# FPGA_Socket.net
KiCad netlist of a schematic drawn in Altium Designer
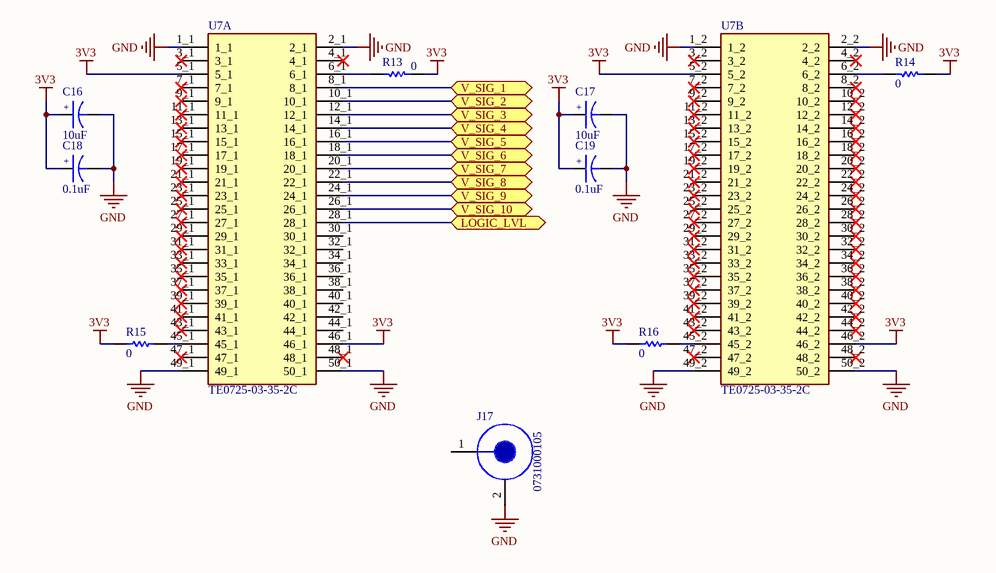
[diagram p0: FPGA_Socket.SchDoc]

(export (version "E")
  (design (tool "Eeschema 10.0.6"))
  (components
    (comp (ref "C16")
      (value "10uF")
      (footprint "0603C")
      (description "Cap Poly")
      (libsource (lib "GENERIC_LIB") (part "CPoly"))
    )
    (comp (ref "C17")
      (value "10uF")
      (footprint "0603C")
      (description "Cap Poly")
      (libsource (lib "GENERIC_LIB") (part "CPoly"))
    )
    (comp (ref "C18")
      (value "0.1uF")
      (footprint "0603C")
      (description "Cap Poly")
      (libsource (lib "GENERIC_LIB") (part "CPoly"))
    )
    (comp (ref "C19")
      (value "0.1uF")
      (footprint "0603C")
      (description "Cap Poly")
      (libsource (lib "GENERIC_LIB") (part "CPoly"))
    )
    (comp (ref "J17")
      (value "0731000105")
      (footprint "0731000105")
      (description "BNC Connector Jack, Female Socket 50Ohm Through Hole, Right Angle Solder")
      (libsource (lib "CON_LIB") (part "0731000105"))
    )
    (comp (ref "R13")
      (value "0")
      (footprint "0603C")
      (description "Resistor")
      (fields (field (name "TOLERANCE") "5%"))
      (libsource (lib "GENERIC_LIB") (part "R"))
    )
    (comp (ref "R14")
      (value "0")
      (footprint "0603C")
      (description "Resistor")
      (fields (field (name "TOLERANCE") "5%"))
      (libsource (lib "GENERIC_LIB") (part "R"))
    )
    (comp (ref "R15")
      (value "0")
      (footprint "0603C")
      (description "Resistor")
      (fields (field (name "TOLERANCE") "5%"))
      (libsource (lib "GENERIC_LIB") (part "R"))
    )
    (comp (ref "R16")
      (value "0")
      (footprint "0603C")
      (description "Resistor")
      (fields (field (name "TOLERANCE") "5%"))
      (libsource (lib "GENERIC_LIB") (part "R"))
    )
    (comp (ref "U7")
      (value "TE0725-03-35-2C")
      (footprint "MODULE_TE0725-03-35-2C")
      (description "TE0725 Embedded Module Artix-7 A35T 100MHz 32MB")
      (fields (field (name "MF") "Trenz Electronic GmbH"))
      (libsource (lib "IC_LOGIC_LIB") (part "TE0725-03-35-2C"))
    )
  )
  (nets
    (net (code "1") (name "/LOGIC_LVL") (class "Default")
      (node (ref "U7") (pin "28_1") (pinfunction "28_1_28_1") (pintype "passive"))
    )
    (net (code "2") (name "/V_SIG_1") (class "Default")
      (node (ref "U7") (pin "8_1") (pinfunction "8_1_8_1") (pintype "passive"))
    )
    (net (code "3") (name "/V_SIG_2") (class "Default")
      (node (ref "U7") (pin "10_1") (pinfunction "10_1_10_1") (pintype "passive"))
    )
    (net (code "4") (name "/V_SIG_3") (class "Default")
      (node (ref "U7") (pin "12_1") (pinfunction "12_1_12_1") (pintype "passive"))
    )
    (net (code "5") (name "/V_SIG_4") (class "Default")
      (node (ref "U7") (pin "14_1") (pinfunction "14_1_14_1") (pintype "passive"))
    )
    (net (code "6") (name "/V_SIG_5") (class "Default")
      (node (ref "U7") (pin "16_1") (pinfunction "16_1_16_1") (pintype "passive"))
    )
    (net (code "7") (name "/V_SIG_6") (class "Default")
      (node (ref "U7") (pin "18_1") (pinfunction "18_1_18_1") (pintype "passive"))
    )
    (net (code "8") (name "/V_SIG_7") (class "Default")
      (node (ref "U7") (pin "20_1") (pinfunction "20_1_20_1") (pintype "passive"))
    )
    (net (code "9") (name "/V_SIG_8") (class "Default")
      (node (ref "U7") (pin "22_1") (pinfunction "22_1_22_1") (pintype "passive"))
    )
    (net (code "10") (name "/V_SIG_9") (class "Default")
      (node (ref "U7") (pin "24_1") (pinfunction "24_1_24_1") (pintype "passive"))
    )
    (net (code "11") (name "/V_SIG_10") (class "Default")
      (node (ref "U7") (pin "26_1") (pinfunction "26_1_26_1") (pintype "passive"))
    )
    (net (code "12") (name "3V3") (class "Default")
      (node (ref "C16") (pin "1") (pinfunction "1_1") (pintype "passive"))
      (node (ref "C17") (pin "1") (pinfunction "1_1") (pintype "passive"))
      (node (ref "C18") (pin "1") (pinfunction "1_1") (pintype "passive"))
      (node (ref "C19") (pin "1") (pinfunction "1_1") (pintype "passive"))
      (node (ref "R13") (pin "1") (pinfunction "1_1") (pintype "passive"))
      (node (ref "R14") (pin "1") (pinfunction "1_1") (pintype "passive"))
      (node (ref "R15") (pin "1") (pinfunction "1_1") (pintype "passive"))
      (node (ref "R16") (pin "1") (pinfunction "1_1") (pintype "passive"))
      (node (ref "U7") (pin "46_1") (pinfunction "46_1_46_1") (pintype "passive"))
      (node (ref "U7") (pin "46_2") (pinfunction "46_2_46_2") (pintype "passive"))
      (node (ref "U7") (pin "5_1") (pinfunction "5_1_5_1") (pintype "passive"))
      (node (ref "U7") (pin "5_2") (pinfunction "5_2_5_2") (pintype "passive"))
    )
    (net (code "13") (name "GND") (class "Default")
      (node (ref "C16") (pin "2") (pinfunction "2_2") (pintype "passive"))
      (node (ref "C17") (pin "2") (pinfunction "2_2") (pintype "passive"))
      (node (ref "C18") (pin "2") (pinfunction "2_2") (pintype "passive"))
      (node (ref "C19") (pin "2") (pinfunction "2_2") (pintype "passive"))
      (node (ref "J17") (pin "2") (pinfunction "2_2") (pintype "passive"))
      (node (ref "U7") (pin "1_1") (pinfunction "1_1_1_1") (pintype "passive"))
      (node (ref "U7") (pin "1_2") (pinfunction "1_2_1_2") (pintype "passive"))
      (node (ref "U7") (pin "2_1") (pinfunction "2_1_2_1") (pintype "passive"))
      (node (ref "U7") (pin "2_2") (pinfunction "2_2_2_2") (pintype "passive"))
      (node (ref "U7") (pin "49_1") (pinfunction "49_1_49_1") (pintype "passive"))
      (node (ref "U7") (pin "49_2") (pinfunction "49_2_49_2") (pintype "passive"))
      (node (ref "U7") (pin "50_1") (pinfunction "50_1_50_1") (pintype "passive"))
      (node (ref "U7") (pin "50_2") (pinfunction "50_2_50_2") (pintype "passive"))
    )
    (net (code "14") (name "Net-(R13-Pad2)") (class "Default")
      (node (ref "R13") (pin "2") (pinfunction "2_2") (pintype "passive"))
      (node (ref "U7") (pin "6_1") (pinfunction "6_1_6_1") (pintype "passive"))
    )
    (net (code "15") (name "Net-(R14-Pad2)") (class "Default")
      (node (ref "R14") (pin "2") (pinfunction "2_2") (pintype "passive"))
      (node (ref "U7") (pin "6_2") (pinfunction "6_2_6_2") (pintype "passive"))
    )
    (net (code "16") (name "Net-(R15-Pad2)") (class "Default")
      (node (ref "R15") (pin "2") (pinfunction "2_2") (pintype "passive"))
      (node (ref "U7") (pin "45_1") (pinfunction "45_1_45_1") (pintype "passive"))
    )
    (net (code "17") (name "Net-(R16-Pad2)") (class "Default")
      (node (ref "R16") (pin "2") (pinfunction "2_2") (pintype "passive"))
      (node (ref "U7") (pin "45_2") (pinfunction "45_2_45_2") (pintype "passive"))
    )
    (net (code "18") (name "unconnected-(J17-Pad1)") (class "Default")
      (node (ref "J17") (pin "1") (pinfunction "1_1") (pintype "passive"))
    )
    (net (code "19") (name "unconnected-(U7-Pad3_1)") (class "Default")
      (node (ref "U7") (pin "3_1") (pinfunction "3_1_3_1") (pintype "passive+no_connect"))
    )
    (net (code "20") (name "unconnected-(U7-Pad3_2)") (class "Default")
      (node (ref "U7") (pin "3_2") (pinfunction "3_2_3_2") (pintype "passive+no_connect"))
    )
    (net (code "21") (name "unconnected-(U7-Pad4_1)") (class "Default")
      (node (ref "U7") (pin "4_1") (pinfunction "4_1_4_1") (pintype "passive+no_connect"))
    )
    (net (code "22") (name "unconnected-(U7-Pad4_2)") (class "Default")
      (node (ref "U7") (pin "4_2") (pinfunction "4_2_4_2") (pintype "passive+no_connect"))
    )
    (net (code "23") (name "unconnected-(U7-Pad7_1)") (class "Default")
      (node (ref "U7") (pin "7_1") (pinfunction "7_1_7_1") (pintype "passive+no_connect"))
    )
    (net (code "24") (name "unconnected-(U7-Pad7_2)") (class "Default")
      (node (ref "U7") (pin "7_2") (pinfunction "7_2_7_2") (pintype "passive+no_connect"))
    )
    (net (code "25") (name "unconnected-(U7-Pad8_2)") (class "Default")
      (node (ref "U7") (pin "8_2") (pinfunction "8_2_8_2") (pintype "passive+no_connect"))
    )
    (net (code "26") (name "unconnected-(U7-Pad9_1)") (class "Default")
      (node (ref "U7") (pin "9_1") (pinfunction "9_1_9_1") (pintype "passive+no_connect"))
    )
    (net (code "27") (name "unconnected-(U7-Pad9_2)") (class "Default")
      (node (ref "U7") (pin "9_2") (pinfunction "9_2_9_2") (pintype "passive+no_connect"))
    )
    (net (code "28") (name "unconnected-(U7-Pad10_2)") (class "Default")
      (node (ref "U7") (pin "10_2") (pinfunction "10_2_10_2") (pintype "passive+no_connect"))
    )
    (net (code "29") (name "unconnected-(U7-Pad11_1)") (class "Default")
      (node (ref "U7") (pin "11_1") (pinfunction "11_1_11_1") (pintype "passive+no_connect"))
    )
    (net (code "30") (name "unconnected-(U7-Pad11_2)") (class "Default")
      (node (ref "U7") (pin "11_2") (pinfunction "11_2_11_2") (pintype "passive+no_connect"))
    )
    (net (code "31") (name "unconnected-(U7-Pad12_2)") (class "Default")
      (node (ref "U7") (pin "12_2") (pinfunction "12_2_12_2") (pintype "passive+no_connect"))
    )
    (net (code "32") (name "unconnected-(U7-Pad13_1)") (class "Default")
      (node (ref "U7") (pin "13_1") (pinfunction "13_1_13_1") (pintype "passive+no_connect"))
    )
    (net (code "33") (name "unconnected-(U7-Pad13_2)") (class "Default")
      (node (ref "U7") (pin "13_2") (pinfunction "13_2_13_2") (pintype "passive+no_connect"))
    )
    (net (code "34") (name "unconnected-(U7-Pad14_2)") (class "Default")
      (node (ref "U7") (pin "14_2") (pinfunction "14_2_14_2") (pintype "passive+no_connect"))
    )
    (net (code "35") (name "unconnected-(U7-Pad15_1)") (class "Default")
      (node (ref "U7") (pin "15_1") (pinfunction "15_1_15_1") (pintype "passive+no_connect"))
    )
    (net (code "36") (name "unconnected-(U7-Pad15_2)") (class "Default")
      (node (ref "U7") (pin "15_2") (pinfunction "15_2_15_2") (pintype "passive+no_connect"))
    )
    (net (code "37") (name "unconnected-(U7-Pad16_2)") (class "Default")
      (node (ref "U7") (pin "16_2") (pinfunction "16_2_16_2") (pintype "passive+no_connect"))
    )
    (net (code "38") (name "unconnected-(U7-Pad17_1)") (class "Default")
      (node (ref "U7") (pin "17_1") (pinfunction "17_1_17_1") (pintype "passive+no_connect"))
    )
    (net (code "39") (name "unconnected-(U7-Pad17_2)") (class "Default")
      (node (ref "U7") (pin "17_2") (pinfunction "17_2_17_2") (pintype "passive+no_connect"))
    )
    (net (code "40") (name "unconnected-(U7-Pad18_2)") (class "Default")
      (node (ref "U7") (pin "18_2") (pinfunction "18_2_18_2") (pintype "passive+no_connect"))
    )
    (net (code "41") (name "unconnected-(U7-Pad19_1)") (class "Default")
      (node (ref "U7") (pin "19_1") (pinfunction "19_1_19_1") (pintype "passive+no_connect"))
    )
    (net (code "42") (name "unconnected-(U7-Pad19_2)") (class "Default")
      (node (ref "U7") (pin "19_2") (pinfunction "19_2_19_2") (pintype "passive+no_connect"))
    )
    (net (code "43") (name "unconnected-(U7-Pad20_2)") (class "Default")
      (node (ref "U7") (pin "20_2") (pinfunction "20_2_20_2") (pintype "passive+no_connect"))
    )
    (net (code "44") (name "unconnected-(U7-Pad21_1)") (class "Default")
      (node (ref "U7") (pin "21_1") (pinfunction "21_1_21_1") (pintype "passive+no_connect"))
    )
    (net (code "45") (name "unconnected-(U7-Pad21_2)") (class "Default")
      (node (ref "U7") (pin "21_2") (pinfunction "21_2_21_2") (pintype "passive+no_connect"))
    )
    (net (code "46") (name "unconnected-(U7-Pad22_2)") (class "Default")
      (node (ref "U7") (pin "22_2") (pinfunction "22_2_22_2") (pintype "passive+no_connect"))
    )
    (net (code "47") (name "unconnected-(U7-Pad23_1)") (class "Default")
      (node (ref "U7") (pin "23_1") (pinfunction "23_1_23_1") (pintype "passive+no_connect"))
    )
    (net (code "48") (name "unconnected-(U7-Pad23_2)") (class "Default")
      (node (ref "U7") (pin "23_2") (pinfunction "23_2_23_2") (pintype "passive+no_connect"))
    )
    (net (code "49") (name "unconnected-(U7-Pad24_2)") (class "Default")
      (node (ref "U7") (pin "24_2") (pinfunction "24_2_24_2") (pintype "passive+no_connect"))
    )
    (net (code "50") (name "unconnected-(U7-Pad25_1)") (class "Default")
      (node (ref "U7") (pin "25_1") (pinfunction "25_1_25_1") (pintype "passive+no_connect"))
    )
    (net (code "51") (name "unconnected-(U7-Pad25_2)") (class "Default")
      (node (ref "U7") (pin "25_2") (pinfunction "25_2_25_2") (pintype "passive+no_connect"))
    )
    (net (code "52") (name "unconnected-(U7-Pad26_2)") (class "Default")
      (node (ref "U7") (pin "26_2") (pinfunction "26_2_26_2") (pintype "passive+no_connect"))
    )
    (net (code "53") (name "unconnected-(U7-Pad27_1)") (class "Default")
      (node (ref "U7") (pin "27_1") (pinfunction "27_1_27_1") (pintype "passive+no_connect"))
    )
    (net (code "54") (name "unconnected-(U7-Pad27_2)") (class "Default")
      (node (ref "U7") (pin "27_2") (pinfunction "27_2_27_2") (pintype "passive+no_connect"))
    )
    (net (code "55") (name "unconnected-(U7-Pad28_2)") (class "Default")
      (node (ref "U7") (pin "28_2") (pinfunction "28_2_28_2") (pintype "passive+no_connect"))
    )
    (net (code "56") (name "unconnected-(U7-Pad29_1)") (class "Default")
      (node (ref "U7") (pin "29_1") (pinfunction "29_1_29_1") (pintype "passive+no_connect"))
    )
    (net (code "57") (name "unconnected-(U7-Pad29_2)") (class "Default")
      (node (ref "U7") (pin "29_2") (pinfunction "29_2_29_2") (pintype "passive+no_connect"))
    )
    (net (code "58") (name "unconnected-(U7-Pad30_1)") (class "Default")
      (node (ref "U7") (pin "30_1") (pinfunction "30_1_30_1") (pintype "passive"))
    )
    (net (code "59") (name "unconnected-(U7-Pad30_2)") (class "Default")
      (node (ref "U7") (pin "30_2") (pinfunction "30_2_30_2") (pintype "passive+no_connect"))
    )
    (net (code "60") (name "unconnected-(U7-Pad31_1)") (class "Default")
      (node (ref "U7") (pin "31_1") (pinfunction "31_1_31_1") (pintype "passive+no_connect"))
    )
    (net (code "61") (name "unconnected-(U7-Pad31_2)") (class "Default")
      (node (ref "U7") (pin "31_2") (pinfunction "31_2_31_2") (pintype "passive+no_connect"))
    )
    (net (code "62") (name "unconnected-(U7-Pad32_1)") (class "Default")
      (node (ref "U7") (pin "32_1") (pinfunction "32_1_32_1") (pintype "passive"))
    )
    (net (code "63") (name "unconnected-(U7-Pad32_2)") (class "Default")
      (node (ref "U7") (pin "32_2") (pinfunction "32_2_32_2") (pintype "passive+no_connect"))
    )
    (net (code "64") (name "unconnected-(U7-Pad33_1)") (class "Default")
      (node (ref "U7") (pin "33_1") (pinfunction "33_1_33_1") (pintype "passive+no_connect"))
    )
    (net (code "65") (name "unconnected-(U7-Pad33_2)") (class "Default")
      (node (ref "U7") (pin "33_2") (pinfunction "33_2_33_2") (pintype "passive+no_connect"))
    )
    (net (code "66") (name "unconnected-(U7-Pad34_1)") (class "Default")
      (node (ref "U7") (pin "34_1") (pinfunction "34_1_34_1") (pintype "passive"))
    )
    (net (code "67") (name "unconnected-(U7-Pad34_2)") (class "Default")
      (node (ref "U7") (pin "34_2") (pinfunction "34_2_34_2") (pintype "passive+no_connect"))
    )
    (net (code "68") (name "unconnected-(U7-Pad35_1)") (class "Default")
      (node (ref "U7") (pin "35_1") (pinfunction "35_1_35_1") (pintype "passive+no_connect"))
    )
    (net (code "69") (name "unconnected-(U7-Pad35_2)") (class "Default")
      (node (ref "U7") (pin "35_2") (pinfunction "35_2_35_2") (pintype "passive+no_connect"))
    )
    (net (code "70") (name "unconnected-(U7-Pad36_1)") (class "Default")
      (node (ref "U7") (pin "36_1") (pinfunction "36_1_36_1") (pintype "passive"))
    )
    (net (code "71") (name "unconnected-(U7-Pad36_2)") (class "Default")
      (node (ref "U7") (pin "36_2") (pinfunction "36_2_36_2") (pintype "passive+no_connect"))
    )
    (net (code "72") (name "unconnected-(U7-Pad37_1)") (class "Default")
      (node (ref "U7") (pin "37_1") (pinfunction "37_1_37_1") (pintype "passive+no_connect"))
    )
    (net (code "73") (name "unconnected-(U7-Pad37_2)") (class "Default")
      (node (ref "U7") (pin "37_2") (pinfunction "37_2_37_2") (pintype "passive+no_connect"))
    )
    (net (code "74") (name "unconnected-(U7-Pad38_1)") (class "Default")
      (node (ref "U7") (pin "38_1") (pinfunction "38_1_38_1") (pintype "passive"))
    )
    (net (code "75") (name "unconnected-(U7-Pad38_2)") (class "Default")
      (node (ref "U7") (pin "38_2") (pinfunction "38_2_38_2") (pintype "passive+no_connect"))
    )
    (net (code "76") (name "unconnected-(U7-Pad39_1)") (class "Default")
      (node (ref "U7") (pin "39_1") (pinfunction "39_1_39_1") (pintype "passive+no_connect"))
    )
    (net (code "77") (name "unconnected-(U7-Pad39_2)") (class "Default")
      (node (ref "U7") (pin "39_2") (pinfunction "39_2_39_2") (pintype "passive+no_connect"))
    )
    (net (code "78") (name "unconnected-(U7-Pad40_1)") (class "Default")
      (node (ref "U7") (pin "40_1") (pinfunction "40_1_40_1") (pintype "passive"))
    )
    (net (code "79") (name "unconnected-(U7-Pad40_2)") (class "Default")
      (node (ref "U7") (pin "40_2") (pinfunction "40_2_40_2") (pintype "passive+no_connect"))
    )
    (net (code "80") (name "unconnected-(U7-Pad41_1)") (class "Default")
      (node (ref "U7") (pin "41_1") (pinfunction "41_1_41_1") (pintype "passive+no_connect"))
    )
    (net (code "81") (name "unconnected-(U7-Pad41_2)") (class "Default")
      (node (ref "U7") (pin "41_2") (pinfunction "41_2_41_2") (pintype "passive+no_connect"))
    )
    (net (code "82") (name "unconnected-(U7-Pad42_1)") (class "Default")
      (node (ref "U7") (pin "42_1") (pinfunction "42_1_42_1") (pintype "passive"))
    )
    (net (code "83") (name "unconnected-(U7-Pad42_2)") (class "Default")
      (node (ref "U7") (pin "42_2") (pinfunction "42_2_42_2") (pintype "passive+no_connect"))
    )
    (net (code "84") (name "unconnected-(U7-Pad43_1)") (class "Default")
      (node (ref "U7") (pin "43_1") (pinfunction "43_1_43_1") (pintype "passive+no_connect"))
    )
    (net (code "85") (name "unconnected-(U7-Pad43_2)") (class "Default")
      (node (ref "U7") (pin "43_2") (pinfunction "43_2_43_2") (pintype "passive+no_connect"))
    )
    (net (code "86") (name "unconnected-(U7-Pad44_1)") (class "Default")
      (node (ref "U7") (pin "44_1") (pinfunction "44_1_44_1") (pintype "passive"))
    )
    (net (code "87") (name "unconnected-(U7-Pad44_2)") (class "Default")
      (node (ref "U7") (pin "44_2") (pinfunction "44_2_44_2") (pintype "passive+no_connect"))
    )
    (net (code "88") (name "unconnected-(U7-Pad47_1)") (class "Default")
      (node (ref "U7") (pin "47_1") (pinfunction "47_1_47_1") (pintype "passive+no_connect"))
    )
    (net (code "89") (name "unconnected-(U7-Pad47_2)") (class "Default")
      (node (ref "U7") (pin "47_2") (pinfunction "47_2_47_2") (pintype "passive+no_connect"))
    )
    (net (code "90") (name "unconnected-(U7-Pad48_1)") (class "Default")
      (node (ref "U7") (pin "48_1") (pinfunction "48_1_48_1") (pintype "passive+no_connect"))
    )
    (net (code "91") (name "unconnected-(U7-Pad48_2)") (class "Default")
      (node (ref "U7") (pin "48_2") (pinfunction "48_2_48_2") (pintype "passive+no_connect"))
    )
  )
)
